# bristol_longshot.net
KiCad netlist of a schematic drawn in EAGLE
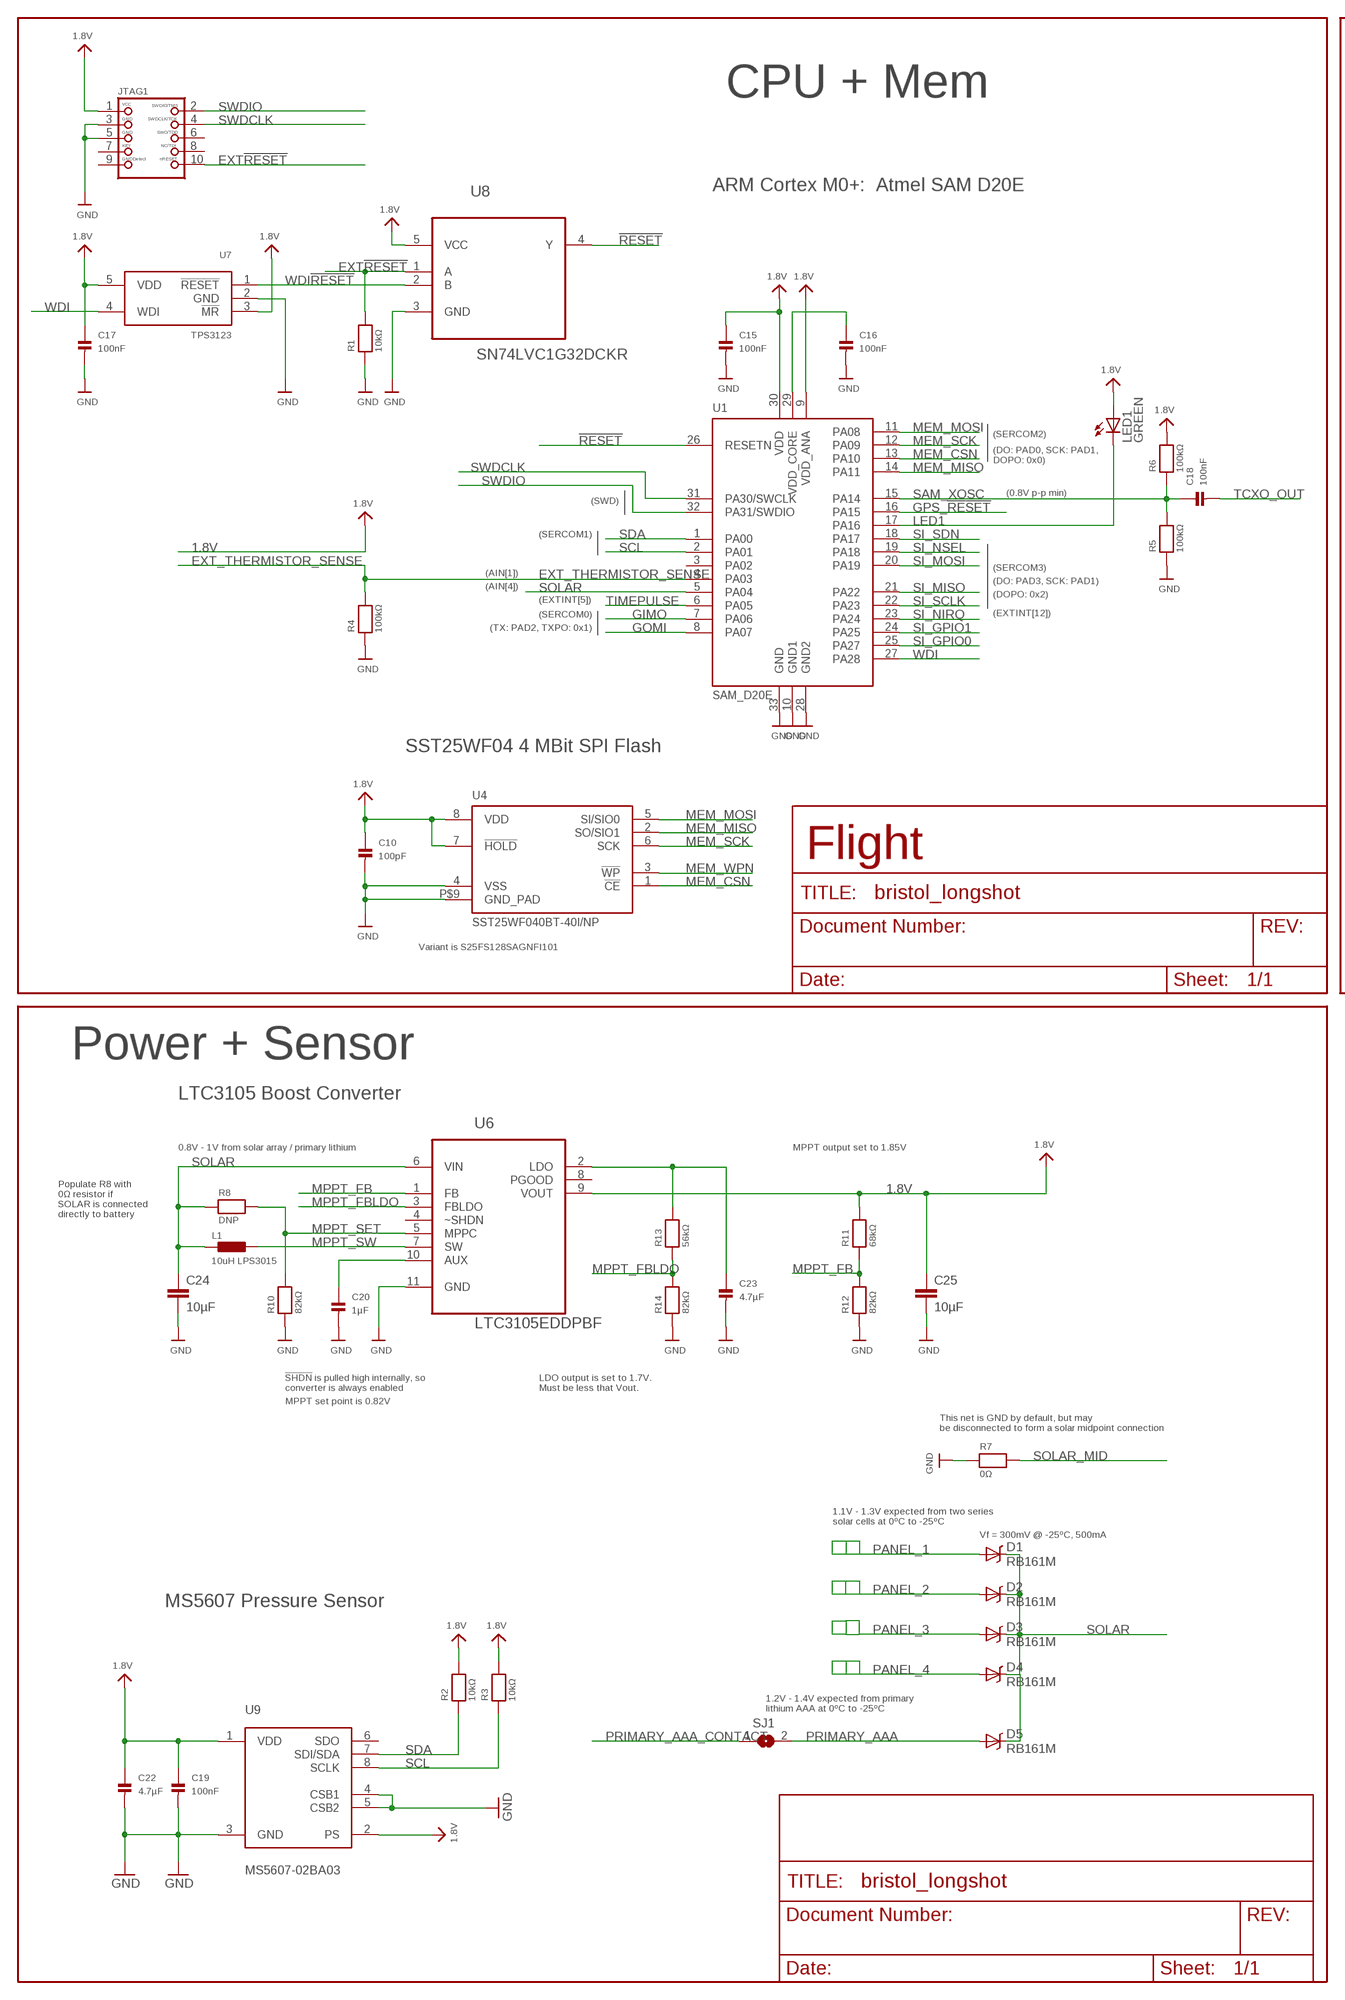
[diagram p0: schematic, sheet 1, part 1 of 2]
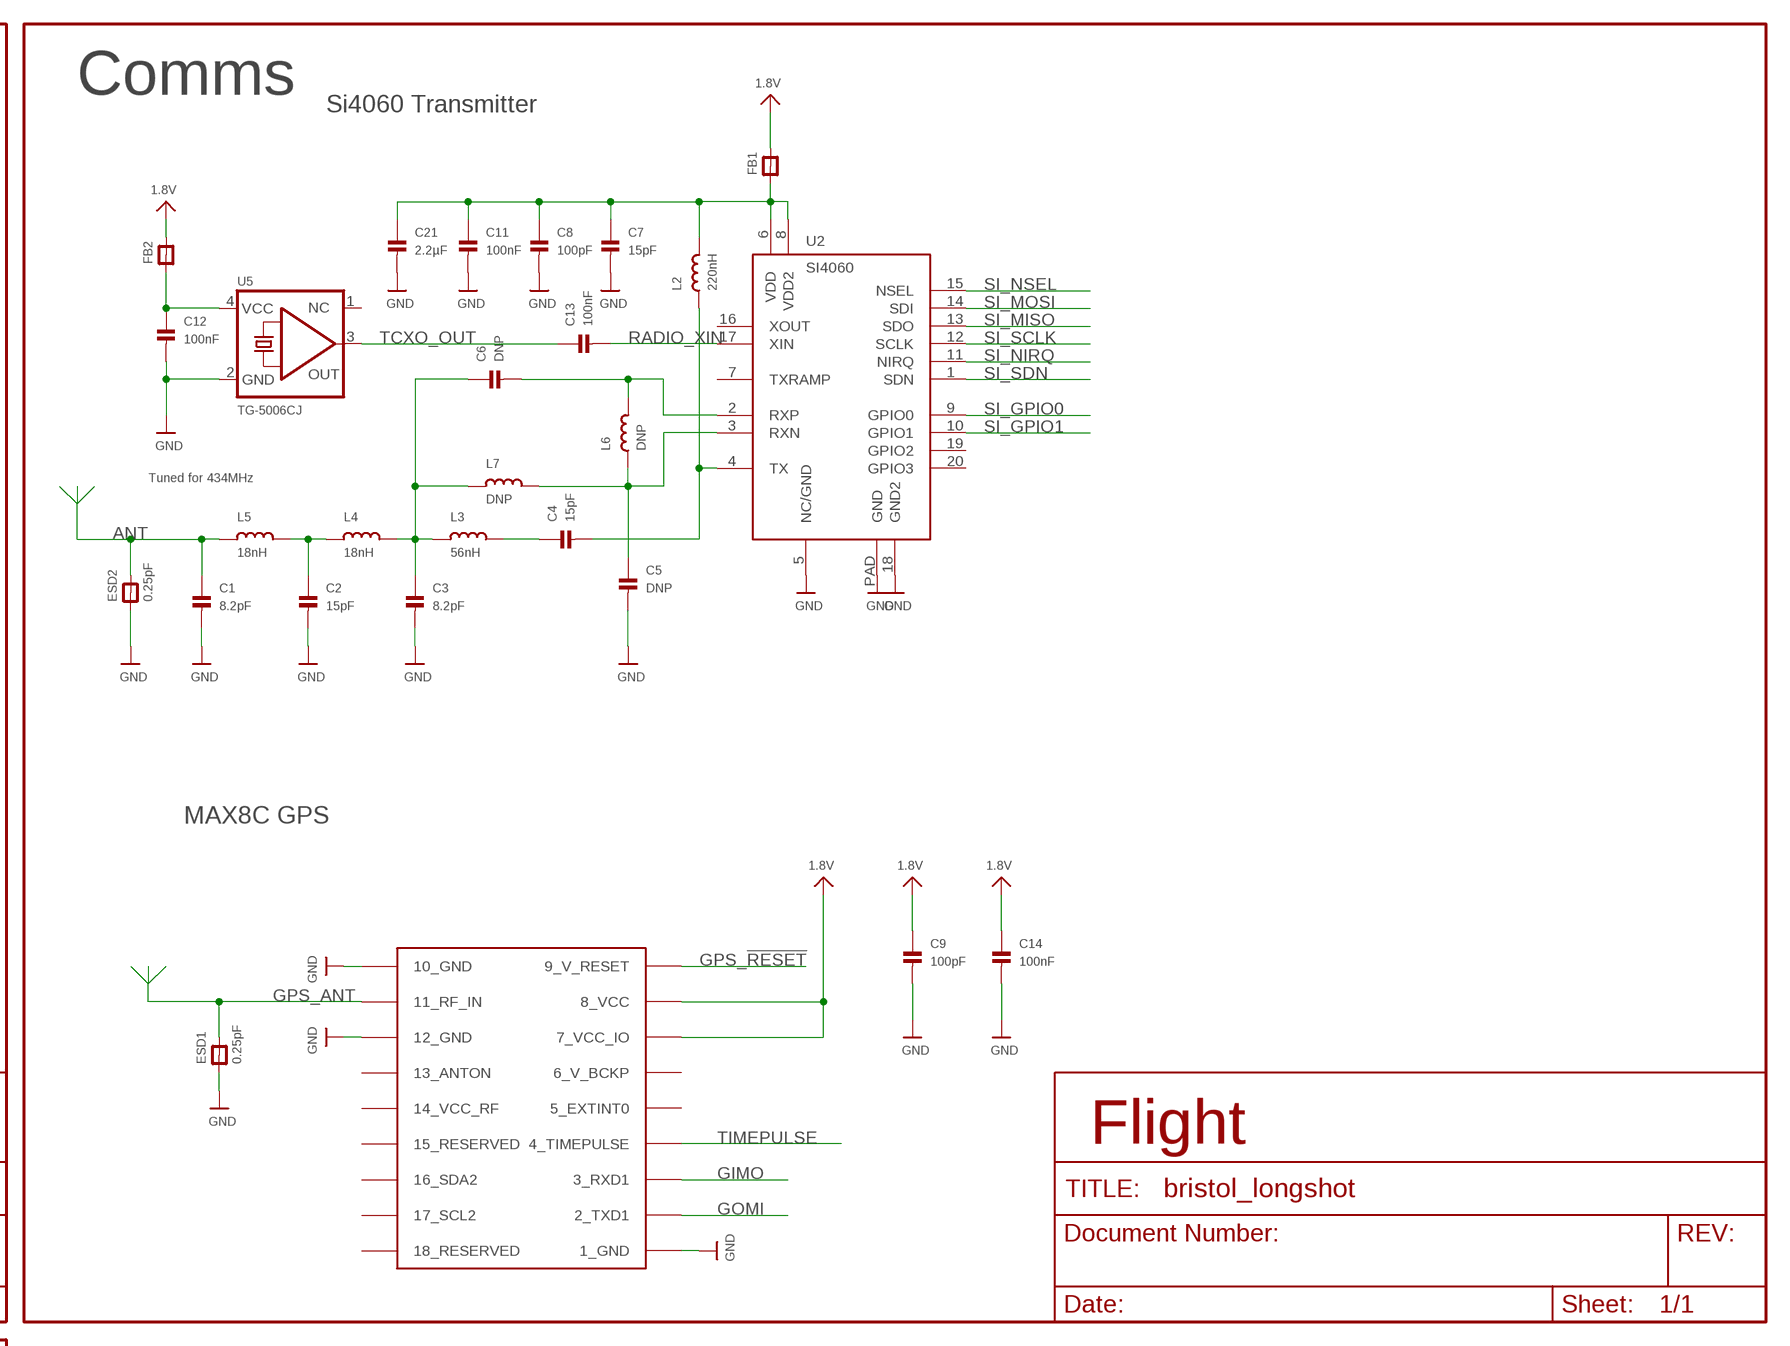
[diagram p1: schematic, sheet 1, part 2 of 2]

(export (version "E")
  (design (tool "Eeschema 10.0.6"))
  (components
    (comp (ref "C1")
      (value "8.2pF")
      (footprint "eagle-import:_0402@1")
      (libsource (lib "eagle-import") (part "CAP_CERAMIC_0402"))
    )
    (comp (ref "C2")
      (value "15pF")
      (footprint "eagle-import:_0402@1")
      (libsource (lib "eagle-import") (part "CAP_CERAMIC_0402"))
    )
    (comp (ref "C3")
      (value "8.2pF")
      (footprint "eagle-import:_0402@1")
      (libsource (lib "eagle-import") (part "CAP_CERAMIC_0402"))
    )
    (comp (ref "C4")
      (value "15pF")
      (footprint "eagle-import:_0402@1")
      (libsource (lib "eagle-import") (part "CAP_CERAMIC_0402"))
    )
    (comp (ref "C5")
      (value "DNP")
      (footprint "eagle-import:_0402@1")
      (libsource (lib "eagle-import") (part "CAP_CERAMIC_0402"))
    )
    (comp (ref "C6")
      (value "DNP")
      (footprint "eagle-import:_0402@1")
      (libsource (lib "eagle-import") (part "CAP_CERAMIC_0402"))
    )
    (comp (ref "C7")
      (value "15pF")
      (footprint "eagle-import:_0402@1")
      (libsource (lib "eagle-import") (part "CAP_CERAMIC_0402"))
    )
    (comp (ref "C8")
      (value "100pF")
      (footprint "eagle-import:_0402@1")
      (libsource (lib "eagle-import") (part "CAP_CERAMIC_0402"))
    )
    (comp (ref "C9")
      (value "100pF")
      (footprint "eagle-import:_0402@1")
      (libsource (lib "eagle-import") (part "CAP_CERAMIC_0402"))
    )
    (comp (ref "C10")
      (value "100pF")
      (footprint "eagle-import:_0402@1")
      (libsource (lib "eagle-import") (part "CAP_CERAMIC_0402"))
    )
    (comp (ref "C11")
      (value "100nF")
      (footprint "eagle-import:_0402@1")
      (libsource (lib "eagle-import") (part "CAP_CERAMIC_0402"))
    )
    (comp (ref "C12")
      (value "100nF")
      (footprint "eagle-import:_0402@1")
      (libsource (lib "eagle-import") (part "CAP_CERAMIC_0402"))
    )
    (comp (ref "C13")
      (value "100nF")
      (footprint "eagle-import:_0402@1")
      (libsource (lib "eagle-import") (part "CAP_CERAMIC_0402"))
    )
    (comp (ref "C14")
      (value "100nF")
      (footprint "eagle-import:_0402@1")
      (libsource (lib "eagle-import") (part "CAP_CERAMIC_0402"))
    )
    (comp (ref "C15")
      (value "100nF")
      (footprint "eagle-import:_0402@1")
      (libsource (lib "eagle-import") (part "CAP_CERAMIC_0402"))
    )
    (comp (ref "C16")
      (value "100nF")
      (footprint "eagle-import:_0402@1")
      (libsource (lib "eagle-import") (part "CAP_CERAMIC_0402"))
    )
    (comp (ref "C17")
      (value "100nF")
      (footprint "eagle-import:_0402@1")
      (libsource (lib "eagle-import") (part "CAP_CERAMIC_0402"))
    )
    (comp (ref "C18")
      (value "100nF")
      (footprint "eagle-import:_0402@1")
      (libsource (lib "eagle-import") (part "CAP_CERAMIC_0402"))
    )
    (comp (ref "C19")
      (value "100nF")
      (footprint "eagle-import:_0402@1")
      (libsource (lib "eagle-import") (part "CAP_CERAMIC_0402"))
    )
    (comp (ref "C20")
      (value "1µF")
      (footprint "eagle-import:_0402@1")
      (libsource (lib "eagle-import") (part "CAP_CERAMIC_0402"))
    )
    (comp (ref "C21")
      (value "2.2µF")
      (footprint "eagle-import:_0402@1")
      (libsource (lib "eagle-import") (part "CAP_CERAMIC_0402"))
    )
    (comp (ref "C22")
      (value "4.7µF")
      (footprint "eagle-import:_0402@1")
      (libsource (lib "eagle-import") (part "CAP_CERAMIC_0402"))
    )
    (comp (ref "C23")
      (value "4.7µF")
      (footprint "eagle-import:_0402@1")
      (libsource (lib "eagle-import") (part "CAP_CERAMIC_0402"))
    )
    (comp (ref "C24")
      (value "10µF")
      (footprint "eagle-import:C0603K")
      (libsource (lib "eagle-import") (part "C-EUC0603K"))
    )
    (comp (ref "C25")
      (value "10µF")
      (footprint "eagle-import:C0603K")
      (libsource (lib "eagle-import") (part "C-EUC0603K"))
    )
    (comp (ref "D1")
      (value "RB161M")
      (footprint "eagle-import:RB161M")
      (libsource (lib "eagle-import") (part "RB161M"))
    )
    (comp (ref "D2")
      (value "RB161M")
      (footprint "eagle-import:RB161M")
      (libsource (lib "eagle-import") (part "RB161M"))
    )
    (comp (ref "D3")
      (value "RB161M")
      (footprint "eagle-import:RB161M")
      (libsource (lib "eagle-import") (part "RB161M"))
    )
    (comp (ref "D4")
      (value "RB161M")
      (footprint "eagle-import:RB161M")
      (libsource (lib "eagle-import") (part "RB161M"))
    )
    (comp (ref "D5")
      (value "RB161M")
      (footprint "eagle-import:RB161M")
      (libsource (lib "eagle-import") (part "RB161M"))
    )
    (comp (ref "ESD1")
      (value "0.25pF")
      (footprint "eagle-import:_0603MP")
      (libsource (lib "eagle-import") (part "FERRITE_0603MP"))
    )
    (comp (ref "ESD2")
      (value "0.25pF")
      (footprint "eagle-import:_0603MP")
      (libsource (lib "eagle-import") (part "FERRITE_0603MP"))
    )
    (comp (ref "FB1")
      (value "FERRITE_0402")
      (footprint "eagle-import:_0402@1")
      (libsource (lib "eagle-import") (part "FERRITE_0402"))
    )
    (comp (ref "FB2")
      (value "FERRITE_0402")
      (footprint "eagle-import:_0402@1")
      (libsource (lib "eagle-import") (part "FERRITE_0402"))
    )
    (comp (ref "JTAG1")
      (value "JTAG-CORTEXM3SMT")
      (footprint "eagle-import:2X05_1.27MM_SMT")
      (libsource (lib "eagle-import") (part "JTAG-CORTEXM3SMT"))
    )
    (comp (ref "L1")
      (value "10uH LPS3015")
      (footprint "eagle-import:LPS3015")
      (libsource (lib "eagle-import") (part "IND-LPS3015"))
    )
    (comp (ref "L2")
      (value "220nH")
      (footprint "eagle-import:_0402@1")
      (libsource (lib "eagle-import") (part "INDUCTOR_0402"))
    )
    (comp (ref "L3")
      (value "56nH")
      (footprint "eagle-import:_0402@1")
      (libsource (lib "eagle-import") (part "INDUCTOR_0402"))
    )
    (comp (ref "L4")
      (value "18nH")
      (footprint "eagle-import:_0402@1")
      (libsource (lib "eagle-import") (part "INDUCTOR_0402"))
    )
    (comp (ref "L5")
      (value "18nH")
      (footprint "eagle-import:_0402@1")
      (libsource (lib "eagle-import") (part "INDUCTOR_0402"))
    )
    (comp (ref "L6")
      (value "DNP")
      (footprint "eagle-import:_0402@1")
      (libsource (lib "eagle-import") (part "INDUCTOR_0402"))
    )
    (comp (ref "L7")
      (value "DNP")
      (footprint "eagle-import:_0402@1")
      (libsource (lib "eagle-import") (part "INDUCTOR_0402"))
    )
    (comp (ref "LED1")
      (value "GREEN")
      (footprint "eagle-import:CHIPLED_0603")
      (libsource (lib "eagle-import") (part "LEDCHIPLED_0603"))
    )
    (comp (ref "R1")
      (value "10kΩ")
      (footprint "eagle-import:_0402")
      (libsource (lib "eagle-import") (part "RESISTOR_0402"))
    )
    (comp (ref "R2")
      (value "10kΩ")
      (footprint "eagle-import:_0402")
      (libsource (lib "eagle-import") (part "RESISTOR_0402"))
    )
    (comp (ref "R3")
      (value "10kΩ")
      (footprint "eagle-import:_0402")
      (libsource (lib "eagle-import") (part "RESISTOR_0402"))
    )
    (comp (ref "R4")
      (value "100kΩ")
      (footprint "eagle-import:_0402")
      (libsource (lib "eagle-import") (part "RESISTOR_0402"))
    )
    (comp (ref "R5")
      (value "100kΩ")
      (footprint "eagle-import:_0402")
      (libsource (lib "eagle-import") (part "RESISTOR_0402"))
    )
    (comp (ref "R6")
      (value "100kΩ")
      (footprint "eagle-import:_0402")
      (libsource (lib "eagle-import") (part "RESISTOR_0402"))
    )
    (comp (ref "R7")
      (value "0Ω")
      (footprint "eagle-import:_0402")
      (libsource (lib "eagle-import") (part "RESISTOR_0402"))
    )
    (comp (ref "R8")
      (value "DNP")
      (footprint "eagle-import:_0402")
      (libsource (lib "eagle-import") (part "RESISTOR_0402"))
    )
    (comp (ref "R10")
      (value "82kΩ")
      (footprint "eagle-import:_0402")
      (libsource (lib "eagle-import") (part "RESISTOR_0402"))
    )
    (comp (ref "R11")
      (value "68kΩ")
      (footprint "eagle-import:_0402")
      (libsource (lib "eagle-import") (part "RESISTOR_0402"))
    )
    (comp (ref "R12")
      (value "82kΩ")
      (footprint "eagle-import:_0402")
      (libsource (lib "eagle-import") (part "RESISTOR_0402"))
    )
    (comp (ref "R13")
      (value "56kΩ")
      (footprint "eagle-import:_0402")
      (libsource (lib "eagle-import") (part "RESISTOR_0402"))
    )
    (comp (ref "R14")
      (value "82kΩ")
      (footprint "eagle-import:_0402")
      (libsource (lib "eagle-import") (part "RESISTOR_0402"))
    )
    (comp (ref "SJ1")
      (value "SOLDERJUMPERREFLOW")
      (footprint "eagle-import:SOLDERJUMPER_REFLOW")
      (libsource (lib "eagle-import") (part "SOLDERJUMPERREFLOW"))
    )
    (comp (ref "U1")
      (value "SAM_D20E")
      (footprint "eagle-import:QFN32_5MM")
      (libsource (lib "eagle-import") (part "SAM_D20E"))
    )
    (comp (ref "U2")
      (value "SI4060")
      (footprint "eagle-import:QFN20")
      (libsource (lib "eagle-import") (part "SI4060"))
    )
    (comp (ref "U3")
      (value "UBLOX_MAX")
      (footprint "eagle-import:UBLOX_MAX")
      (libsource (lib "eagle-import") (part "UBLOX_MAX"))
    )
    (comp (ref "U4")
      (value "SST25WF040BT-40I/NP")
      (footprint "eagle-import:USON-8")
      (libsource (lib "eagle-import") (part "SST25WF040BT-40I/NP"))
    )
    (comp (ref "U5")
      (value "TG-5006CJ")
      (footprint "eagle-import:TC-5006CJ")
      (libsource (lib "eagle-import") (part "TG-5006CJ"))
    )
    (comp (ref "U6")
      (value "LTC3105EDDPBF")
      (footprint "eagle-import:DFN300X300X80-11N")
      (fields (field (name "MPN") "LTC3105EDD#PBF"))
      (libsource (lib "eagle-import") (part "LTC3105EDDPBF"))
    )
    (comp (ref "U7")
      (value "TPS3123")
      (footprint "eagle-import:SOT23-5")
      (libsource (lib "eagle-import") (part "TPS3123"))
    )
    (comp (ref "U8")
      (value "SN74LVC1G32DCKR")
      (footprint "eagle-import:SOT65P210X110-5N")
      (libsource (lib "eagle-import") (part "SN74LVC1G32DCKR"))
    )
    (comp (ref "U9")
      (value "MS5607-02BA03")
      (footprint "eagle-import:MS5607-02BA03")
      (libsource (lib "eagle-import") (part "MS5607-02BA03"))
    )
  )
  (nets
    (net (code "1") (name "/ANT") (class "Default")
      (node (ref "C1") (pin "1") (pinfunction "P$1_1") (pintype "passive"))
      (node (ref "ESD2") (pin "2") (pinfunction "P$2_2") (pintype "passive"))
      (node (ref "L5") (pin "1") (pinfunction "1_1") (pintype "passive"))
    )
    (net (code "2") (name "/EXT_THERMISTOR_SENSE") (class "Default")
      (node (ref "R4") (pin "2") (pinfunction "2_2") (pintype "passive"))
      (node (ref "U1") (pin "4") (pinfunction "PA03_4") (pintype "bidirectional"))
    )
    (net (code "3") (name "/EXT~{RESET}") (class "Default")
      (node (ref "JTAG1") (pin "10") (pinfunction "10_10") (pintype "passive"))
      (node (ref "R1") (pin "2") (pinfunction "2_2") (pintype "passive"))
      (node (ref "U8") (pin "1") (pinfunction "A_1") (pintype "input"))
    )
    (net (code "4") (name "/GIMO") (class "Default")
      (node (ref "U1") (pin "7") (pinfunction "PA06_7") (pintype "bidirectional"))
      (node (ref "U3") (pin "3_RXD1") (pinfunction "3_RXD1_3_RXD1") (pintype "bidirectional"))
    )
    (net (code "5") (name "/GOMI") (class "Default")
      (node (ref "U1") (pin "8") (pinfunction "PA07_8") (pintype "bidirectional"))
      (node (ref "U3") (pin "2_TXD1") (pinfunction "2_TXD1_2_TXD1") (pintype "bidirectional"))
    )
    (net (code "6") (name "/GPS_ANT") (class "Default")
      (node (ref "ESD1") (pin "2") (pinfunction "P$2_2") (pintype "passive"))
      (node (ref "U3") (pin "11_RF_IN") (pinfunction "11_RF_IN_11_RF_IN") (pintype "bidirectional"))
    )
    (net (code "7") (name "/GPS_~{RESET}") (class "Default")
      (node (ref "U1") (pin "16") (pinfunction "PA15_16") (pintype "bidirectional"))
      (node (ref "U3") (pin "9_V_RESET") (pinfunction "9_V_RESET_9_V_RESET") (pintype "power_in"))
    )
    (net (code "8") (name "/LED1") (class "Default")
      (node (ref "LED1") (pin "C") (pinfunction "C_C") (pintype "passive"))
      (node (ref "U1") (pin "17") (pinfunction "PA16_17") (pintype "bidirectional"))
    )
    (net (code "9") (name "/MEM_CSN") (class "Default")
      (node (ref "U1") (pin "13") (pinfunction "PA10_13") (pintype "bidirectional"))
      (node (ref "U4") (pin "1") (pinfunction "~{CE}_1") (pintype "input"))
    )
    (net (code "10") (name "/MEM_MISO") (class "Default")
      (node (ref "U1") (pin "14") (pinfunction "PA11_14") (pintype "bidirectional"))
      (node (ref "U4") (pin "2") (pinfunction "SO/SIO1_2") (pintype "output"))
    )
    (net (code "11") (name "/MEM_MOSI") (class "Default")
      (node (ref "U1") (pin "11") (pinfunction "PA08_11") (pintype "bidirectional"))
      (node (ref "U4") (pin "5") (pinfunction "SI/SIO0_5") (pintype "bidirectional"))
    )
    (net (code "12") (name "/MEM_SCK") (class "Default")
      (node (ref "U1") (pin "12") (pinfunction "PA09_12") (pintype "bidirectional"))
      (node (ref "U4") (pin "6") (pinfunction "SCK_6") (pintype "input"))
    )
    (net (code "13") (name "/MEM_WPN") (class "Default")
      (node (ref "U4") (pin "3") (pinfunction "~{WP}_3") (pintype "output"))
    )
    (net (code "14") (name "/MPPT_FB") (class "Default")
      (node (ref "R11") (pin "1") (pinfunction "1_1") (pintype "passive"))
      (node (ref "R12") (pin "2") (pinfunction "2_2") (pintype "passive"))
      (node (ref "U6") (pin "1") (pinfunction "FB_1") (pintype "input"))
    )
    (net (code "15") (name "/MPPT_FBLDO") (class "Default")
      (node (ref "R13") (pin "1") (pinfunction "1_1") (pintype "passive"))
      (node (ref "R14") (pin "2") (pinfunction "2_2") (pintype "passive"))
      (node (ref "U6") (pin "3") (pinfunction "FBLDO_3") (pintype "input"))
    )
    (net (code "16") (name "/MPPT_SET") (class "Default")
      (node (ref "R10") (pin "2") (pinfunction "2_2") (pintype "passive"))
      (node (ref "R8") (pin "2") (pinfunction "2_2") (pintype "passive"))
      (node (ref "U6") (pin "5") (pinfunction "MPPC_5") (pintype "input"))
    )
    (net (code "17") (name "/MPPT_SW") (class "Default")
      (node (ref "L1") (pin "2_1") (pinfunction "2_2_1") (pintype "passive"))
      (node (ref "L1") (pin "2_2") (pinfunction "2_2_2") (pintype "passive"))
      (node (ref "L1") (pin "2_3") (pinfunction "2_2_3") (pintype "passive"))
      (node (ref "L1") (pin "2_4") (pinfunction "2_2_4") (pintype "passive"))
      (node (ref "L1") (pin "2_5") (pinfunction "2_2_5") (pintype "passive"))
      (node (ref "L1") (pin "2_6") (pinfunction "2_2_6") (pintype "passive"))
      (node (ref "L1") (pin "2_7") (pinfunction "2_2_7") (pintype "passive"))
      (node (ref "L1") (pin "2_8") (pinfunction "2_2_8") (pintype "passive"))
      (node (ref "L1") (pin "2_9") (pinfunction "2_2_9") (pintype "passive"))
      (node (ref "U6") (pin "7") (pinfunction "SW_7") (pintype "passive"))
    )
    (net (code "18") (name "/PANEL_1") (class "Default")
      (node (ref "D1") (pin "ANODE") (pinfunction "A_ANODE") (pintype "passive"))
    )
    (net (code "19") (name "/PANEL_2") (class "Default")
      (node (ref "D2") (pin "ANODE") (pinfunction "A_ANODE") (pintype "passive"))
    )
    (net (code "20") (name "/PANEL_3") (class "Default")
      (node (ref "D3") (pin "ANODE") (pinfunction "A_ANODE") (pintype "passive"))
    )
    (net (code "21") (name "/PANEL_4") (class "Default")
      (node (ref "D4") (pin "ANODE") (pinfunction "A_ANODE") (pintype "passive"))
    )
    (net (code "22") (name "/PRIMARY_AAA") (class "Default")
      (node (ref "D5") (pin "ANODE") (pinfunction "A_ANODE") (pintype "passive"))
      (node (ref "SJ1") (pin "2") (pinfunction "2_2") (pintype "passive"))
    )
    (net (code "23") (name "/PRIMARY_AAA_CONTACT") (class "Default")
      (node (ref "SJ1") (pin "1") (pinfunction "1_1") (pintype "passive"))
    )
    (net (code "24") (name "/RADIO_XIN") (class "Default")
      (node (ref "C13") (pin "2") (pinfunction "P$2_2") (pintype "passive"))
      (node (ref "U2") (pin "17") (pinfunction "XIN_17") (pintype "input"))
    )
    (net (code "25") (name "/SAM_XOSC") (class "Default")
      (node (ref "C18") (pin "1") (pinfunction "P$1_1") (pintype "passive"))
      (node (ref "R5") (pin "2") (pinfunction "2_2") (pintype "passive"))
      (node (ref "R6") (pin "1") (pinfunction "1_1") (pintype "passive"))
      (node (ref "U1") (pin "15") (pinfunction "PA14_15") (pintype "bidirectional"))
    )
    (net (code "26") (name "/SCL") (class "Default")
      (node (ref "R3") (pin "1") (pinfunction "1_1") (pintype "passive"))
      (node (ref "U1") (pin "2") (pinfunction "PA01_2") (pintype "bidirectional"))
      (node (ref "U9") (pin "8") (pinfunction "SCLK_8") (pintype "bidirectional"))
    )
    (net (code "27") (name "/SDA") (class "Default")
      (node (ref "R2") (pin "1") (pinfunction "1_1") (pintype "passive"))
      (node (ref "U1") (pin "1") (pinfunction "PA00_1") (pintype "bidirectional"))
      (node (ref "U9") (pin "7") (pinfunction "SDI/SDA_7") (pintype "bidirectional"))
    )
    (net (code "28") (name "/SI_GPIO0") (class "Default")
      (node (ref "U1") (pin "25") (pinfunction "PA27_25") (pintype "bidirectional"))
      (node (ref "U2") (pin "9") (pinfunction "GPIO0_9") (pintype "bidirectional"))
    )
    (net (code "29") (name "/SI_GPIO1") (class "Default")
      (node (ref "U1") (pin "24") (pinfunction "PA25_24") (pintype "bidirectional"))
      (node (ref "U2") (pin "10") (pinfunction "GPIO1_10") (pintype "bidirectional"))
    )
    (net (code "30") (name "/SI_MISO") (class "Default")
      (node (ref "U1") (pin "21") (pinfunction "PA22_21") (pintype "bidirectional"))
      (node (ref "U2") (pin "13") (pinfunction "SDO_13") (pintype "output"))
    )
    (net (code "31") (name "/SI_MOSI") (class "Default")
      (node (ref "U1") (pin "20") (pinfunction "PA19_20") (pintype "bidirectional"))
      (node (ref "U2") (pin "14") (pinfunction "SDI_14") (pintype "bidirectional"))
    )
    (net (code "32") (name "/SI_NIRQ") (class "Default")
      (node (ref "U1") (pin "23") (pinfunction "PA24_23") (pintype "bidirectional"))
      (node (ref "U2") (pin "11") (pinfunction "NIRQ_11") (pintype "output"))
    )
    (net (code "33") (name "/SI_NSEL") (class "Default")
      (node (ref "U1") (pin "19") (pinfunction "PA18_19") (pintype "bidirectional"))
      (node (ref "U2") (pin "15") (pinfunction "NSEL_15") (pintype "input"))
    )
    (net (code "34") (name "/SI_SCLK") (class "Default")
      (node (ref "U1") (pin "22") (pinfunction "PA23_22") (pintype "bidirectional"))
      (node (ref "U2") (pin "12") (pinfunction "SCLK_12") (pintype "input"))
    )
    (net (code "35") (name "/SI_SDN") (class "Default")
      (node (ref "U1") (pin "18") (pinfunction "PA17_18") (pintype "bidirectional"))
      (node (ref "U2") (pin "1") (pinfunction "SDN_1") (pintype "input"))
    )
    (net (code "36") (name "/SOLAR") (class "Default")
      (node (ref "C24") (pin "1") (pinfunction "1_1") (pintype "passive"))
      (node (ref "D1") (pin "CATHODE") (pinfunction "C_CATHODE") (pintype "passive"))
      (node (ref "D2") (pin "CATHODE") (pinfunction "C_CATHODE") (pintype "passive"))
      (node (ref "D3") (pin "CATHODE") (pinfunction "C_CATHODE") (pintype "passive"))
      (node (ref "D4") (pin "CATHODE") (pinfunction "C_CATHODE") (pintype "passive"))
      (node (ref "D5") (pin "CATHODE") (pinfunction "C_CATHODE") (pintype "passive"))
      (node (ref "L1") (pin "1_1") (pinfunction "1_1_1") (pintype "passive"))
      (node (ref "L1") (pin "1_2") (pinfunction "1_1_2") (pintype "passive"))
      (node (ref "L1") (pin "1_3") (pinfunction "1_1_3") (pintype "passive"))
      (node (ref "L1") (pin "1_4") (pinfunction "1_1_4") (pintype "passive"))
      (node (ref "L1") (pin "1_5") (pinfunction "1_1_5") (pintype "passive"))
      (node (ref "L1") (pin "1_6") (pinfunction "1_1_6") (pintype "passive"))
      (node (ref "L1") (pin "1_7") (pinfunction "1_1_7") (pintype "passive"))
      (node (ref "L1") (pin "1_8") (pinfunction "1_1_8") (pintype "passive"))
      (node (ref "L1") (pin "1_9") (pinfunction "1_1_9") (pintype "passive"))
      (node (ref "R8") (pin "1") (pinfunction "1_1") (pintype "passive"))
      (node (ref "U1") (pin "5") (pinfunction "PA04_5") (pintype "bidirectional"))
      (node (ref "U6") (pin "6") (pinfunction "VIN_6") (pintype "power_in"))
    )
    (net (code "37") (name "/SOLAR_MID") (class "Default")
      (node (ref "R7") (pin "2") (pinfunction "2_2") (pintype "passive"))
    )
    (net (code "38") (name "/SWDCLK") (class "Default")
      (node (ref "JTAG1") (pin "4") (pinfunction "4_4") (pintype "passive"))
      (node (ref "U1") (pin "31") (pinfunction "PA30/SWCLK_31") (pintype "bidirectional"))
    )
    (net (code "39") (name "/SWDIO") (class "Default")
      (node (ref "JTAG1") (pin "2") (pinfunction "2_2") (pintype "passive"))
      (node (ref "U1") (pin "32") (pinfunction "PA31/SWDIO_32") (pintype "bidirectional"))
    )
    (net (code "40") (name "/TCXO_OUT") (class "Default")
      (node (ref "C13") (pin "1") (pinfunction "P$1_1") (pintype "passive"))
      (node (ref "C18") (pin "2") (pinfunction "P$2_2") (pintype "passive"))
      (node (ref "U5") (pin "3") (pinfunction "OUT_3") (pintype "output"))
    )
    (net (code "41") (name "/TIMEPULSE") (class "Default")
      (node (ref "U1") (pin "6") (pinfunction "PA05_6") (pintype "bidirectional"))
      (node (ref "U3") (pin "4_TIMEPULSE") (pinfunction "4_TIMEPULSE_4_TIMEPULSE") (pintype "bidirectional"))
    )
    (net (code "42") (name "/WDI") (class "Default")
      (node (ref "U1") (pin "27") (pinfunction "PA28_27") (pintype "bidirectional"))
      (node (ref "U7") (pin "4") (pinfunction "WDI_4") (pintype "bidirectional"))
    )
    (net (code "43") (name "/WDI~{RESET}") (class "Default")
      (node (ref "U7") (pin "1") (pinfunction "~{RESET}_1") (pintype "bidirectional"))
      (node (ref "U8") (pin "2") (pinfunction "B_2") (pintype "input"))
    )
    (net (code "44") (name "/~{RESET}") (class "Default")
      (node (ref "U1") (pin "26") (pinfunction "RESETN_26") (pintype "input"))
      (node (ref "U8") (pin "4") (pinfunction "Y_4") (pintype "output"))
    )
    (net (code "45") (name "1.8V") (class "Default")
      (node (ref "C10") (pin "1") (pinfunction "P$1_1") (pintype "passive"))
      (node (ref "C14") (pin "1") (pinfunction "P$1_1") (pintype "passive"))
      (node (ref "C15") (pin "1") (pinfunction "P$1_1") (pintype "passive"))
      (node (ref "C17") (pin "1") (pinfunction "P$1_1") (pintype "passive"))
      (node (ref "C19") (pin "1") (pinfunction "P$1_1") (pintype "passive"))
      (node (ref "C22") (pin "1") (pinfunction "P$1_1") (pintype "passive"))
      (node (ref "C25") (pin "1") (pinfunction "1_1") (pintype "passive"))
      (node (ref "C9") (pin "1") (pinfunction "P$1_1") (pintype "passive"))
      (node (ref "FB1") (pin "2") (pinfunction "P$2_2") (pintype "passive"))
      (node (ref "FB2") (pin "2") (pinfunction "P$2_2") (pintype "passive"))
      (node (ref "JTAG1") (pin "1") (pinfunction "1_1") (pintype "passive"))
      (node (ref "LED1") (pin "A") (pinfunction "A_A") (pintype "passive"))
      (node (ref "R11") (pin "2") (pinfunction "2_2") (pintype "passive"))
      (node (ref "R2") (pin "2") (pinfunction "2_2") (pintype "passive"))
      (node (ref "R3") (pin "2") (pinfunction "2_2") (pintype "passive"))
      (node (ref "R6") (pin "2") (pinfunction "2_2") (pintype "passive"))
      (node (ref "U1") (pin "30") (pinfunction "VDD_30") (pintype "power_in"))
      (node (ref "U1") (pin "9") (pinfunction "VDD_ANA_9") (pintype "power_in"))
      (node (ref "U3") (pin "7_VCC_IO") (pinfunction "7_VCC_IO_7_VCC_IO") (pintype "power_in"))
      (node (ref "U3") (pin "8_VCC") (pinfunction "8_VCC_8_VCC") (pintype "power_in"))
      (node (ref "U4") (pin "7") (pinfunction "~{HOLD}_7") (pintype "output"))
      (node (ref "U4") (pin "8") (pinfunction "VDD_8") (pintype "power_in"))
      (node (ref "U6") (pin "9") (pinfunction "VOUT_9") (pintype "output"))
      (node (ref "U7") (pin "3") (pinfunction "~{MR}_3") (pintype "bidirectional"))
      (node (ref "U7") (pin "5") (pinfunction "VDD_5") (pintype "bidirectional"))
      (node (ref "U8") (pin "5") (pinfunction "VCC_5") (pintype "power_in"))
      (node (ref "U9") (pin "1") (pinfunction "VDD_1") (pintype "bidirectional"))
      (node (ref "U9") (pin "2") (pinfunction "PS_2") (pintype "bidirectional"))
    )
    (net (code "46") (name "GND") (class "Default")
      (node (ref "C1") (pin "2") (pinfunction "P$2_2") (pintype "passive"))
      (node (ref "C10") (pin "2") (pinfunction "P$2_2") (pintype "passive"))
      (node (ref "C11") (pin "2") (pinfunction "P$2_2") (pintype "passive"))
      (node (ref "C12") (pin "2") (pinfunction "P$2_2") (pintype "passive"))
      (node (ref "C14") (pin "2") (pinfunction "P$2_2") (pintype "passive"))
      (node (ref "C15") (pin "2") (pinfunction "P$2_2") (pintype "passive"))
      (node (ref "C16") (pin "2") (pinfunction "P$2_2") (pintype "passive"))
      (node (ref "C17") (pin "2") (pinfunction "P$2_2") (pintype "passive"))
      (node (ref "C19") (pin "2") (pinfunction "P$2_2") (pintype "passive"))
      (node (ref "C2") (pin "2") (pinfunction "P$2_2") (pintype "passive"))
      (node (ref "C20") (pin "2") (pinfunction "P$2_2") (pintype "passive"))
      (node (ref "C21") (pin "2") (pinfunction "P$2_2") (pintype "passive"))
      (node (ref "C22") (pin "2") (pinfunction "P$2_2") (pintype "passive"))
      (node (ref "C23") (pin "2") (pinfunction "P$2_2") (pintype "passive"))
      (node (ref "C24") (pin "2") (pinfunction "2_2") (pintype "passive"))
      (node (ref "C25") (pin "2") (pinfunction "2_2") (pintype "passive"))
      (node (ref "C3") (pin "2") (pinfunction "P$2_2") (pintype "passive"))
      (node (ref "C5") (pin "2") (pinfunction "P$2_2") (pintype "passive"))
      (node (ref "C7") (pin "2") (pinfunction "P$2_2") (pintype "passive"))
      (node (ref "C8") (pin "2") (pinfunction "P$2_2") (pintype "passive"))
      (node (ref "C9") (pin "2") (pinfunction "P$2_2") (pintype "passive"))
      (node (ref "ESD1") (pin "1") (pinfunction "P$1_1") (pintype "passive"))
      (node (ref "ESD2") (pin "1") (pinfunction "P$1_1") (pintype "passive"))
      (node (ref "JTAG1") (pin "3") (pinfunction "3_3") (pintype "passive"))
      (node (ref "JTAG1") (pin "5") (pinfunction "5_5") (pintype "passive"))
      (node (ref "R1") (pin "1") (pinfunction "1_1") (pintype "passive"))
      (node (ref "R10") (pin "1") (pinfunction "1_1") (pintype "passive"))
      (node (ref "R12") (pin "1") (pinfunction "1_1") (pintype "passive"))
      (node (ref "R14") (pin "1") (pinfunction "1_1") (pintype "passive"))
      (node (ref "R4") (pin "1") (pinfunction "1_1") (pintype "passive"))
      (node (ref "R5") (pin "1") (pinfunction "1_1") (pintype "passive"))
      (node (ref "R7") (pin "1") (pinfunction "1_1") (pintype "passive"))
      (node (ref "U1") (pin "10") (pinfunction "GND1_10") (pintype "power_in"))
      (node (ref "U1") (pin "28") (pinfunction "GND2_28") (pintype "power_in"))
      (node (ref "U1") (pin "33") (pinfunction "GND_33") (pintype "power_in"))
      (node (ref "U2") (pin "18") (pinfunction "GND2_18") (pintype "power_in"))
      (node (ref "U2") (pin "5") (pinfunction "NC/GND_5") (pintype "bidirectional"))
      (node (ref "U2") (pin "PAD") (pinfunction "GND_PAD") (pintype "power_in"))
      (node (ref "U3") (pin "10_GND") (pinfunction "10_GND_10_GND") (pintype "power_in"))
      (node (ref "U3") (pin "12_GND") (pinfunction "12_GND_12_GND") (pintype "power_in"))
      (node (ref "U3") (pin "1_GND") (pinfunction "1_GND_1_GND") (pintype "power_in"))
      (node (ref "U4") (pin "4") (pinfunction "VSS_4") (pintype "power_in"))
      (node (ref "U4") (pin "P$9") (pinfunction "GND_PAD_P$9") (pintype "power_in"))
      (node (ref "U5") (pin "2") (pinfunction "GND_2") (pintype "power_in"))
      (node (ref "U6") (pin "11") (pinfunction "GND_11") (pintype "passive"))
      (node (ref "U7") (pin "2") (pinfunction "GND_2") (pintype "bidirectional"))
      (node (ref "U8") (pin "3") (pinfunction "GND_3") (pintype "passive"))
      (node (ref "U9") (pin "3") (pinfunction "GND_3") (pintype "bidirectional"))
      (node (ref "U9") (pin "4") (pinfunction "CSB1_4") (pintype "bidirectional"))
      (node (ref "U9") (pin "5") (pinfunction "CSB2_5") (pintype "bidirectional"))
    )
    (net (code "47") (name "Net-(C2-P$1)") (class "Default")
      (node (ref "C2") (pin "1") (pinfunction "P$1_1") (pintype "passive"))
      (node (ref "L4") (pin "1") (pinfunction "1_1") (pintype "passive"))
      (node (ref "L5") (pin "2") (pinfunction "2_2") (pintype "passive"))
    )
    (net (code "48") (name "Net-(C3-P$1)") (class "Default")
      (node (ref "C3") (pin "1") (pinfunction "P$1_1") (pintype "passive"))
      (node (ref "C6") (pin "1") (pinfunction "P$1_1") (pintype "passive"))
      (node (ref "L3") (pin "1") (pinfunction "1_1") (pintype "passive"))
      (node (ref "L4") (pin "2") (pinfunction "2_2") (pintype "passive"))
      (node (ref "L7") (pin "1") (pinfunction "1_1") (pintype "passive"))
    )
    (net (code "49") (name "Net-(C4-P$1)") (class "Default")
      (node (ref "C4") (pin "1") (pinfunction "P$1_1") (pintype "passive"))
      (node (ref "L3") (pin "2") (pinfunction "2_2") (pintype "passive"))
    )
    (net (code "50") (name "Net-(C4-P$2)") (class "Default")
      (node (ref "C4") (pin "2") (pinfunction "P$2_2") (pintype "passive"))
      (node (ref "L2") (pin "1") (pinfunction "1_1") (pintype "passive"))
      (node (ref "U2") (pin "4") (pinfunction "TX_4") (pintype "output"))
    )
    (net (code "51") (name "Net-(C5-P$1)") (class "Default")
      (node (ref "C5") (pin "1") (pinfunction "P$1_1") (pintype "passive"))
      (node (ref "L6") (pin "1") (pinfunction "1_1") (pintype "passive"))
      (node (ref "L7") (pin "2") (pinfunction "2_2") (pintype "passive"))
      (node (ref "U2") (pin "3") (pinfunction "RXN_3") (pintype "input"))
    )
    (net (code "52") (name "Net-(C6-P$2)") (class "Default")
      (node (ref "C6") (pin "2") (pinfunction "P$2_2") (pintype "passive"))
      (node (ref "L6") (pin "2") (pinfunction "2_2") (pintype "passive"))
      (node (ref "U2") (pin "2") (pinfunction "RXP_2") (pintype "input"))
    )
    (net (code "53") (name "Net-(C11-P$1)") (class "Default")
      (node (ref "C11") (pin "1") (pinfunction "P$1_1") (pintype "passive"))
      (node (ref "C21") (pin "1") (pinfunction "P$1_1") (pintype "passive"))
      (node (ref "C7") (pin "1") (pinfunction "P$1_1") (pintype "passive"))
      (node (ref "C8") (pin "1") (pinfunction "P$1_1") (pintype "passive"))
      (node (ref "FB1") (pin "1") (pinfunction "P$1_1") (pintype "passive"))
      (node (ref "L2") (pin "2") (pinfunction "2_2") (pintype "passive"))
      (node (ref "U2") (pin "6") (pinfunction "VDD_6") (pintype "power_in"))
      (node (ref "U2") (pin "8") (pinfunction "VDD2_8") (pintype "power_in"))
    )
    (net (code "54") (name "Net-(C12-P$1)") (class "Default")
      (node (ref "C12") (pin "1") (pinfunction "P$1_1") (pintype "passive"))
      (node (ref "FB2") (pin "1") (pinfunction "P$1_1") (pintype "passive"))
      (node (ref "U5") (pin "4") (pinfunction "VCC_4") (pintype "power_in"))
    )
    (net (code "55") (name "Net-(C16-P$1)") (class "Default")
      (node (ref "C16") (pin "1") (pinfunction "P$1_1") (pintype "passive"))
      (node (ref "U1") (pin "29") (pinfunction "VDD_CORE_29") (pintype "power_in"))
    )
    (net (code "56") (name "Net-(C20-P$1)") (class "Default")
      (node (ref "C20") (pin "1") (pinfunction "P$1_1") (pintype "passive"))
      (node (ref "U6") (pin "10") (pinfunction "AUX_10") (pintype "passive"))
    )
    (net (code "57") (name "Net-(C23-P$1)") (class "Default")
      (node (ref "C23") (pin "1") (pinfunction "P$1_1") (pintype "passive"))
      (node (ref "R13") (pin "2") (pinfunction "2_2") (pintype "passive"))
      (node (ref "U6") (pin "2") (pinfunction "LDO_2") (pintype "output"))
    )
    (net (code "58") (name "unconnected-(JTAG1-Pad6)") (class "Default")
      (node (ref "JTAG1") (pin "6") (pinfunction "6_6") (pintype "passive"))
    )
    (net (code "59") (name "unconnected-(JTAG1-Pad7)") (class "Default")
      (node (ref "JTAG1") (pin "7") (pinfunction "7_7") (pintype "passive"))
    )
    (net (code "60") (name "unconnected-(JTAG1-Pad8)") (class "Default")
      (node (ref "JTAG1") (pin "8") (pinfunction "8_8") (pintype "passive"))
    )
    (net (code "61") (name "unconnected-(JTAG1-Pad9)") (class "Default")
      (node (ref "JTAG1") (pin "9") (pinfunction "9_9") (pintype "passive"))
    )
    (net (code "62") (name "unconnected-(U1-PA02-Pad3)") (class "Default")
      (node (ref "U1") (pin "3") (pinfunction "PA02_3") (pintype "bidirectional"))
    )
    (net (code "63") (name "unconnected-(U2-GPIO2-Pad19)") (class "Default")
      (node (ref "U2") (pin "19") (pinfunction "GPIO2_19") (pintype "bidirectional"))
    )
    (net (code "64") (name "unconnected-(U2-GPIO3-Pad20)") (class "Default")
      (node (ref "U2") (pin "20") (pinfunction "GPIO3_20") (pintype "bidirectional"))
    )
    (net (code "65") (name "unconnected-(U2-TXRAMP-Pad7)") (class "Default")
      (node (ref "U2") (pin "7") (pinfunction "TXRAMP_7") (pintype "bidirectional"))
    )
    (net (code "66") (name "unconnected-(U2-XOUT-Pad16)") (class "Default")
      (node (ref "U2") (pin "16") (pinfunction "XOUT_16") (pintype "output"))
    )
    (net (code "67") (name "unconnected-(U3-Pad5_EXTINT0)") (class "Default")
      (node (ref "U3") (pin "5_EXTINT0") (pinfunction "5_EXTINT0_5_EXTINT0") (pintype "bidirectional"))
    )
    (net (code "68") (name "unconnected-(U3-Pad6_V_BCKP)") (class "Default")
      (node (ref "U3") (pin "6_V_BCKP") (pinfunction "6_V_BCKP_6_V_BCKP") (pintype "bidirectional"))
    )
    (net (code "69") (name "unconnected-(U3-Pad13_ANTON)") (class "Default")
      (node (ref "U3") (pin "13_ANTON") (pinfunction "13_ANTON_13_ANTON") (pintype "bidirectional"))
    )
    (net (code "70") (name "unconnected-(U3-Pad14_VCC_RF)") (class "Default")
      (node (ref "U3") (pin "14_VCC_RF") (pinfunction "14_VCC_RF_14_VCC_RF") (pintype "bidirectional"))
    )
    (net (code "71") (name "unconnected-(U3-Pad15_RESERVED)") (class "Default")
      (node (ref "U3") (pin "15_RESERVED") (pinfunction "15_RESERVED_15_RESERVED") (pintype "bidirectional"))
    )
    (net (code "72") (name "unconnected-(U3-Pad16_SDA2)") (class "Default")
      (node (ref "U3") (pin "16_SDA2") (pinfunction "16_SDA2_16_SDA2") (pintype "bidirectional"))
    )
    (net (code "73") (name "unconnected-(U3-Pad17_SCL2)") (class "Default")
      (node (ref "U3") (pin "17_SCL2") (pinfunction "17_SCL2_17_SCL2") (pintype "bidirectional"))
    )
    (net (code "74") (name "unconnected-(U3-Pad18_RESERVED)") (class "Default")
      (node (ref "U3") (pin "18_RESERVED") (pinfunction "18_RESERVED_18_RESERVED") (pintype "bidirectional"))
    )
    (net (code "75") (name "unconnected-(U5-NC-Pad1)") (class "Default")
      (node (ref "U5") (pin "1") (pinfunction "NC_1") (pintype "no_connect"))
    )
    (net (code "76") (name "unconnected-(U6-PGOOD-Pad8)") (class "Default")
      (node (ref "U6") (pin "8") (pinfunction "PGOOD_8") (pintype "output"))
    )
    (net (code "77") (name "unconnected-(U6-~{SHDN}-Pad4)") (class "Default")
      (node (ref "U6") (pin "4") (pinfunction "~{SHDN}_4") (pintype "input"))
    )
    (net (code "78") (name "unconnected-(U9-SDO-Pad6)") (class "Default")
      (node (ref "U9") (pin "6") (pinfunction "SDO_6") (pintype "bidirectional"))
    )
  )
)
